# PDOC.net
KiCad netlist of a schematic drawn in Altium Designer
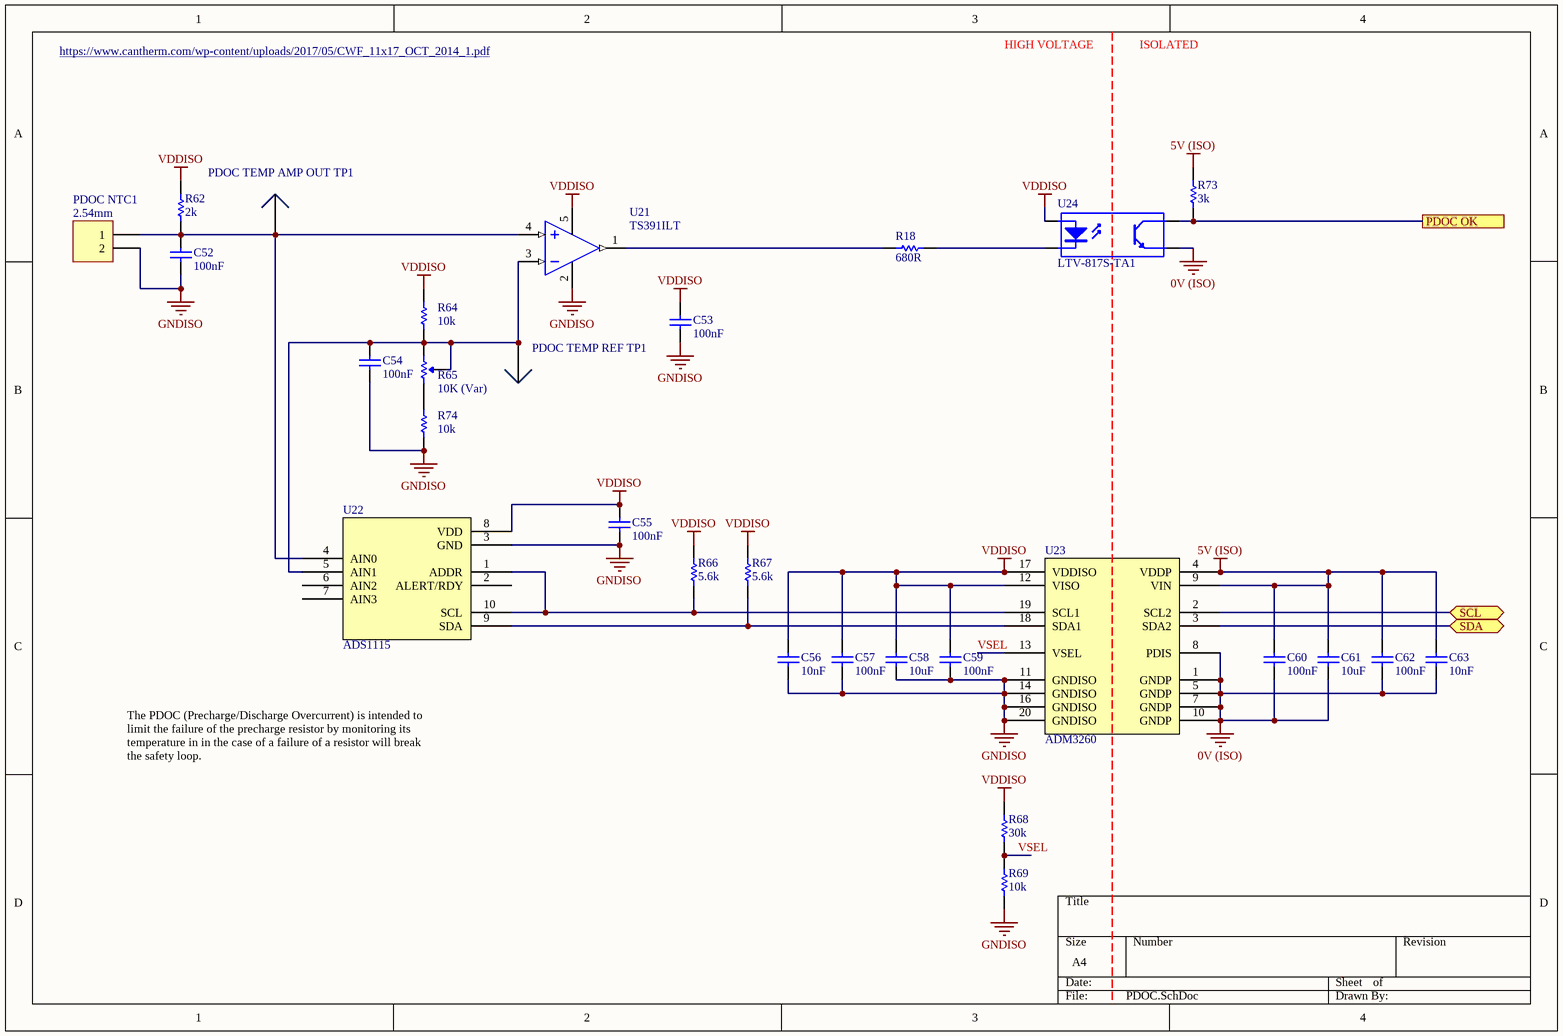
[diagram p0: PDOC.SchDoc]

(export (version "E")
  (design (tool "Eeschema 10.0.6"))
  (components
    (comp (ref "C52")
      (value "100nF")
      (footprint "0805")
      (fields
        (field (name "PART NUMBER") "GCM21BR71H104KA37L")
        (field (name "TOLERANCE") "±10%")
        (field (name "MANUFACTURER") "muRata")
      )
      (libsource (lib "ts_20-standard-library") (part "Capacitor"))
    )
    (comp (ref "C53")
      (value "100nF")
      (footprint "0805")
      (fields
        (field (name "PART NUMBER") "GCM21BR71H104KA37L")
        (field (name "TOLERANCE") "±10%")
        (field (name "MANUFACTURER") "muRata")
      )
      (libsource (lib "ts_20-standard-library") (part "Capacitor"))
    )
    (comp (ref "C54")
      (value "100nF")
      (footprint "0805")
      (fields
        (field (name "PART NUMBER") "GCM21BR71H104KA37L")
        (field (name "TOLERANCE") "±10%")
        (field (name "MANUFACTURER") "muRata")
      )
      (libsource (lib "ts_20-standard-library") (part "Capacitor"))
    )
    (comp (ref "C55")
      (value "100nF")
      (footprint "0805")
      (fields
        (field (name "PART NUMBER") "GCM21BR71H104KA37L")
        (field (name "TOLERANCE") "±10%")
        (field (name "MANUFACTURER") "muRata")
      )
      (libsource (lib "ts_20-standard-library") (part "Capacitor"))
    )
    (comp (ref "C56")
      (value "10nF")
      (footprint "0805")
      (fields
        (field (name "PART NUMBER") "GCM2195C1H103JA16D")
        (field (name "TOLERANCE") "±5%")
        (field (name "MANUFACTURER") "muRata")
      )
      (libsource (lib "ts_20-standard-library") (part "Capacitor"))
    )
    (comp (ref "C57")
      (value "100nF")
      (footprint "0805")
      (fields
        (field (name "PART NUMBER") "GCM21BR71H104KA37L")
        (field (name "TOLERANCE") "±10%")
        (field (name "MANUFACTURER") "muRata")
      )
      (libsource (lib "ts_20-standard-library") (part "Capacitor"))
    )
    (comp (ref "C58")
      (value "10uF")
      (footprint "0805")
      (fields
        (field (name "PART NUMBER") "GRM21BR6YA106KE43L")
        (field (name "TOLERANCE") "10%")
        (field (name "MANUFACTURER") "muRata")
      )
      (libsource (lib "ts_20-standard-library") (part "Capacitor"))
    )
    (comp (ref "C59")
      (value "100nF")
      (footprint "0805")
      (fields
        (field (name "PART NUMBER") "GCM21BR71H104KA37L")
        (field (name "TOLERANCE") "±10%")
        (field (name "MANUFACTURER") "muRata")
      )
      (libsource (lib "ts_20-standard-library") (part "Capacitor"))
    )
    (comp (ref "C60")
      (value "100nF")
      (footprint "0805")
      (fields
        (field (name "PART NUMBER") "GCM21BR71H104KA37L")
        (field (name "TOLERANCE") "±10%")
        (field (name "MANUFACTURER") "muRata")
      )
      (libsource (lib "ts_20-standard-library") (part "Capacitor"))
    )
    (comp (ref "C61")
      (value "10uF")
      (footprint "0805")
      (fields
        (field (name "PART NUMBER") "GRM21BR6YA106KE43L")
        (field (name "TOLERANCE") "10%")
        (field (name "MANUFACTURER") "muRata")
      )
      (libsource (lib "ts_20-standard-library") (part "Capacitor"))
    )
    (comp (ref "C62")
      (value "100nF")
      (footprint "0805")
      (fields
        (field (name "PART NUMBER") "GCM21BR71H104KA37L")
        (field (name "TOLERANCE") "±10%")
        (field (name "MANUFACTURER") "muRata")
      )
      (libsource (lib "ts_20-standard-library") (part "Capacitor"))
    )
    (comp (ref "C63")
      (value "10nF")
      (footprint "0805")
      (fields
        (field (name "PART NUMBER") "GCM2195C1H103JA16D")
        (field (name "TOLERANCE") "±5%")
        (field (name "MANUFACTURER") "muRata")
      )
      (libsource (lib "ts_20-standard-library") (part "Capacitor"))
    )
    (comp (ref "PDOC NTC1")
      (value "2.54mm")
      (footprint "TH 2.54mm Header 1x2")
      (fields (field (name "PART NUMBER") "TH 2.54mm Header 1x2") (field (name "CONTACT") "NA"))
      (libsource (lib "ts_20-standard-connectors") (part "Header 1x2"))
    )
    (comp (ref "PDOC TEMP AMP OUT TP1")
      (value "0mm")
      (footprint "SMD Test Point")
      (fields (field (name "PART NUMBER") "SMD Test Point") (field (name "CONTACT") "NA"))
      (libsource (lib "ts_20-standard-connectors") (part "Test Point"))
    )
    (comp (ref "PDOC TEMP REF TP1")
      (value "0mm")
      (footprint "SMD Test Point")
      (fields (field (name "PART NUMBER") "SMD Test Point") (field (name "CONTACT") "NA"))
      (libsource (lib "ts_20-standard-connectors") (part "Test Point"))
    )
    (comp (ref "R18")
      (value "680R")
      (footprint "0805")
      (fields
        (field (name "PART NUMBER") "RC0805FR07680RL")
        (field (name "MANUFACTURER") "YAGEO")
        (field (name "TOLERANCE") "0.01")
      )
      (libsource (lib "ts_20-standard-library") (part "Resistor"))
    )
    (comp (ref "R62")
      (value "2k")
      (footprint "0805")
      (fields
        (field (name "PART NUMBER") "RC0805FR072KL")
        (field (name "MANUFACTURER") "YAGEO")
        (field (name "TOLERANCE") "0.01")
      )
      (libsource (lib "ts_20-standard-library") (part "Resistor"))
    )
    (comp (ref "R64")
      (value "10k")
      (footprint "0805")
      (fields
        (field (name "PART NUMBER") "RC0805FR0710KL")
        (field (name "MANUFACTURER") "YAGEO")
        (field (name "TOLERANCE") "0.01")
      )
      (libsource (lib "ts_20-standard-library") (part "Resistor"))
    )
    (comp (ref "R65")
      (value "10K (Var)")
      (footprint "B 3296")
      (fields
        (field (name "PART NUMBER") "3296W-1-103LF")
        (field (name "MANUFACTURER") "Bournes Inc")
        (field (name "TOLERANCE") "0.1")
      )
      (libsource (lib "ts_20-standard-library") (part "Resistor (Potentiometer)"))
    )
    (comp (ref "R66")
      (value "5.6k")
      (footprint "0805")
      (fields
        (field (name "PART NUMBER") "RC0805FR075K6L")
        (field (name "MANUFACTURER") "YAGEO")
        (field (name "TOLERANCE") "0.01")
      )
      (libsource (lib "ts_20-standard-library") (part "Resistor"))
    )
    (comp (ref "R67")
      (value "5.6k")
      (footprint "0805")
      (fields
        (field (name "PART NUMBER") "RC0805FR075K6L")
        (field (name "MANUFACTURER") "YAGEO")
        (field (name "TOLERANCE") "0.01")
      )
      (libsource (lib "ts_20-standard-library") (part "Resistor"))
    )
    (comp (ref "R68")
      (value "30k")
      (footprint "0805")
      (fields
        (field (name "PART NUMBER") "RC0805FR0730KL")
        (field (name "MANUFACTURER") "YAGEO")
        (field (name "TOLERANCE") "0.01")
      )
      (libsource (lib "ts_20-standard-library") (part "Resistor"))
    )
    (comp (ref "R69")
      (value "10k")
      (footprint "0805")
      (fields
        (field (name "PART NUMBER") "RC0805FR0710KL")
        (field (name "MANUFACTURER") "YAGEO")
        (field (name "TOLERANCE") "0.01")
      )
      (libsource (lib "ts_20-standard-library") (part "Resistor"))
    )
    (comp (ref "R73")
      (value "3k")
      (footprint "0805")
      (fields
        (field (name "PART NUMBER") "RC0805FR073KL")
        (field (name "MANUFACTURER") "YAGEO")
        (field (name "TOLERANCE") "0.01")
      )
      (libsource (lib "ts_20-standard-library") (part "Resistor"))
    )
    (comp (ref "R74")
      (value "10k")
      (footprint "0805")
      (fields
        (field (name "PART NUMBER") "RC0805FR0710KL")
        (field (name "MANUFACTURER") "YAGEO")
        (field (name "TOLERANCE") "0.01")
      )
      (libsource (lib "ts_20-standard-library") (part "Resistor"))
    )
    (comp (ref "U21")
      (value "TS391ILT")
      (footprint "ON SOT-23-5")
      (description "IC COMP LO PWR SGL V SOT 23-5L")
      (fields
        (field (name "MANUFACTURER") "STMicroelectronics")
        (field (name "DIGIKEY PART NUMBER") "497-2275-2-ND")
      )
      (libsource (lib "ts_20-standard-library") (part "TS391ILT"))
    )
    (comp (ref "U22")
      (value "ADS1115")
      (footprint "TI 10-VSSOP")
      (description "16 Bit Analog to Digital Converter 2, 4 Input 1 Sigma-Delta 10-VSSOP")
      (fields
        (field (name "MANUFACTURER") "Texas Instruments")
        (field (name "DIGIKEY PART NUMBER") "296-38849-1-ND")
      )
      (libsource (lib "ts_20-standard-library") (part "ADS1115"))
    )
    (comp (ref "U23")
      (value "ADM3260")
      (footprint "AD 20-SSOP")
      (description "I²C Digital Isolator 2500Vrms 2 Channel 25kV/µs CMTI 20-SSOP (0.209\", 5.30mm Width)")
      (fields
        (field (name "MANUFACTURER") "Analog Devices")
        (field (name "DIGIKEY PART NUMBER") "ADM3260ARSZ-RL7CT-ND")
      )
      (libsource (lib "ts_20-standard-library") (part "ADM3260"))
    )
    (comp (ref "U24")
      (value "LTV-817S-TA1")
      (footprint "ON 4-SMD")
      (description "35V 50ma Optocoupler (VF=1.2V)")
      (fields
        (field (name "MANUFACTURER") "Lite-On Inc")
        (field (name "DIGIKEY PART NUMBER") "160-1893-2-ND")
      )
      (libsource (lib "ts_20-standard-library") (part "LTV-817S-TA1"))
    )
  )
  (nets
    (net (code "1") (name "/PDOC OK") (class "Default")
      (node (ref "R73") (pin "1") (pinfunction "1_1") (pintype "passive"))
      (node (ref "U24") (pin "4") (pinfunction "C_4") (pintype "passive"))
    )
    (net (code "2") (name "/SCL") (class "Default")
      (node (ref "U23") (pin "2") (pinfunction "SCL2_2") (pintype "passive"))
    )
    (net (code "3") (name "/SDA") (class "Default")
      (node (ref "U23") (pin "3") (pinfunction "SDA2_3") (pintype "passive"))
    )
    (net (code "4") (name "/VSEL") (class "Default")
      (node (ref "R68") (pin "1") (pinfunction "1_1") (pintype "passive"))
      (node (ref "R69") (pin "2") (pinfunction "2_2") (pintype "passive"))
      (node (ref "U23") (pin "13") (pinfunction "VSEL_13") (pintype "passive"))
    )
    (net (code "5") (name "0V (ISO)") (class "Default")
      (node (ref "C60") (pin "1") (pinfunction "1_1") (pintype "passive"))
      (node (ref "C61") (pin "1") (pinfunction "1_1") (pintype "passive"))
      (node (ref "C62") (pin "1") (pinfunction "1_1") (pintype "passive"))
      (node (ref "C63") (pin "1") (pinfunction "1_1") (pintype "passive"))
      (node (ref "U23") (pin "1") (pinfunction "GNDP_1") (pintype "passive"))
      (node (ref "U23") (pin "10") (pinfunction "GNDP_10") (pintype "passive"))
      (node (ref "U23") (pin "5") (pinfunction "GNDP_5") (pintype "passive"))
      (node (ref "U23") (pin "7") (pinfunction "GNDP_7") (pintype "passive"))
      (node (ref "U23") (pin "8") (pinfunction "PDIS_8") (pintype "passive"))
      (node (ref "U24") (pin "3") (pinfunction "E_3") (pintype "passive"))
    )
    (net (code "6") (name "5V (ISO)") (class "Default")
      (node (ref "C60") (pin "2") (pinfunction "2_2") (pintype "passive"))
      (node (ref "C61") (pin "2") (pinfunction "2_2") (pintype "passive"))
      (node (ref "C62") (pin "2") (pinfunction "2_2") (pintype "passive"))
      (node (ref "C63") (pin "2") (pinfunction "2_2") (pintype "passive"))
      (node (ref "R73") (pin "2") (pinfunction "2_2") (pintype "passive"))
      (node (ref "U23") (pin "4") (pinfunction "VDDP_4") (pintype "passive"))
      (node (ref "U23") (pin "9") (pinfunction "VIN_9") (pintype "passive"))
    )
    (net (code "7") (name "GNDISO") (class "Default")
      (node (ref "C52") (pin "1") (pinfunction "1_1") (pintype "passive"))
      (node (ref "C53") (pin "1") (pinfunction "1_1") (pintype "passive"))
      (node (ref "C54") (pin "1") (pinfunction "1_1") (pintype "passive"))
      (node (ref "C55") (pin "2") (pinfunction "2_2") (pintype "passive"))
      (node (ref "C56") (pin "1") (pinfunction "1_1") (pintype "passive"))
      (node (ref "C57") (pin "1") (pinfunction "1_1") (pintype "passive"))
      (node (ref "C58") (pin "1") (pinfunction "1_1") (pintype "passive"))
      (node (ref "C59") (pin "2") (pinfunction "2_2") (pintype "passive"))
      (node (ref "PDOC NTC1") (pin "2") (pinfunction "2_2") (pintype "passive"))
      (node (ref "R69") (pin "1") (pinfunction "1_1") (pintype "passive"))
      (node (ref "R74") (pin "1") (pinfunction "1_1") (pintype "passive"))
      (node (ref "U21") (pin "2") (pinfunction "VCC-_2") (pintype "power_in"))
      (node (ref "U22") (pin "3") (pinfunction "GND_3") (pintype "passive"))
      (node (ref "U23") (pin "11") (pinfunction "GNDISO_11") (pintype "passive"))
      (node (ref "U23") (pin "14") (pinfunction "GNDISO_14") (pintype "passive"))
      (node (ref "U23") (pin "16") (pinfunction "GNDISO_16") (pintype "passive"))
      (node (ref "U23") (pin "20") (pinfunction "GNDISO_20") (pintype "passive"))
    )
    (net (code "8") (name "Net-(R65-CCW)") (class "Default")
      (node (ref "C54") (pin "2") (pinfunction "2_2") (pintype "passive"))
      (node (ref "PDOC TEMP REF TP1") (pin "1") (pinfunction "1_1") (pintype "passive"))
      (node (ref "R64") (pin "1") (pinfunction "1_1") (pintype "passive"))
      (node (ref "R65") (pin "1") (pinfunction "CCW_1") (pintype "passive"))
      (node (ref "R65") (pin "2") (pinfunction "Wiper_2") (pintype "passive"))
      (node (ref "U21") (pin "3") (pinfunction "IN-_3") (pintype "input"))
      (node (ref "U22") (pin "5") (pinfunction "AIN1_5") (pintype "passive"))
    )
    (net (code "9") (name "Net-(R65-CW)") (class "Default")
      (node (ref "R65") (pin "3") (pinfunction "CW_3") (pintype "passive"))
      (node (ref "R74") (pin "2") (pinfunction "2_2") (pintype "passive"))
    )
    (net (code "10") (name "Net-(U21-IIN+)") (class "Default")
      (node (ref "C52") (pin "2") (pinfunction "2_2") (pintype "passive"))
      (node (ref "PDOC NTC1") (pin "1") (pinfunction "1_1") (pintype "passive"))
      (node (ref "PDOC TEMP AMP OUT TP1") (pin "1") (pinfunction "1_1") (pintype "passive"))
      (node (ref "R62") (pin "1") (pinfunction "1_1") (pintype "passive"))
      (node (ref "U21") (pin "4") (pinfunction "IIN+_4") (pintype "input"))
      (node (ref "U22") (pin "4") (pinfunction "AIN0_4") (pintype "passive"))
    )
    (net (code "11") (name "Net-(U21-OUT)") (class "Default")
      (node (ref "R18") (pin "1") (pinfunction "1_1") (pintype "passive"))
      (node (ref "U21") (pin "1") (pinfunction "OUT_1") (pintype "output"))
    )
    (net (code "12") (name "Net-(U22-ADDR)") (class "Default")
      (node (ref "R66") (pin "1") (pinfunction "1_1") (pintype "passive"))
      (node (ref "U22") (pin "1") (pinfunction "ADDR_1") (pintype "passive"))
      (node (ref "U22") (pin "10") (pinfunction "SCL_10") (pintype "passive"))
      (node (ref "U23") (pin "19") (pinfunction "SCL1_19") (pintype "passive"))
    )
    (net (code "13") (name "Net-(U22-SDA)") (class "Default")
      (node (ref "R67") (pin "1") (pinfunction "1_1") (pintype "passive"))
      (node (ref "U22") (pin "9") (pinfunction "SDA_9") (pintype "passive"))
      (node (ref "U23") (pin "18") (pinfunction "SDA1_18") (pintype "passive"))
    )
    (net (code "14") (name "Net-(U24-K)") (class "Default")
      (node (ref "R18") (pin "2") (pinfunction "2_2") (pintype "passive"))
      (node (ref "U24") (pin "2") (pinfunction "K_2") (pintype "passive"))
    )
    (net (code "15") (name "VDDISO") (class "Default")
      (node (ref "C53") (pin "2") (pinfunction "2_2") (pintype "passive"))
      (node (ref "C55") (pin "1") (pinfunction "1_1") (pintype "passive"))
      (node (ref "C56") (pin "2") (pinfunction "2_2") (pintype "passive"))
      (node (ref "C57") (pin "2") (pinfunction "2_2") (pintype "passive"))
      (node (ref "C58") (pin "2") (pinfunction "2_2") (pintype "passive"))
      (node (ref "C59") (pin "1") (pinfunction "1_1") (pintype "passive"))
      (node (ref "R62") (pin "2") (pinfunction "2_2") (pintype "passive"))
      (node (ref "R64") (pin "2") (pinfunction "2_2") (pintype "passive"))
      (node (ref "R66") (pin "2") (pinfunction "2_2") (pintype "passive"))
      (node (ref "R67") (pin "2") (pinfunction "2_2") (pintype "passive"))
      (node (ref "R68") (pin "2") (pinfunction "2_2") (pintype "passive"))
      (node (ref "U21") (pin "5") (pinfunction "VCC+_5") (pintype "power_in"))
      (node (ref "U22") (pin "8") (pinfunction "VDD_8") (pintype "passive"))
      (node (ref "U23") (pin "12") (pinfunction "VISO_12") (pintype "passive"))
      (node (ref "U23") (pin "17") (pinfunction "VDDISO_17") (pintype "passive"))
      (node (ref "U24") (pin "1") (pinfunction "A_1") (pintype "passive"))
    )
    (net (code "16") (name "unconnected-(U22-AIN2-Pad6)") (class "Default")
      (node (ref "U22") (pin "6") (pinfunction "AIN2_6") (pintype "passive"))
    )
    (net (code "17") (name "unconnected-(U22-AIN3-Pad7)") (class "Default")
      (node (ref "U22") (pin "7") (pinfunction "AIN3_7") (pintype "passive"))
    )
    (net (code "18") (name "unconnected-(U22-ALERT{slash}RDY-Pad2)") (class "Default")
      (node (ref "U22") (pin "2") (pinfunction "ALERT/RDY_2") (pintype "passive"))
    )
  )
)
